# TRN_Open_Servo.net
KiCad netlist of a schematic drawn in EAGLE
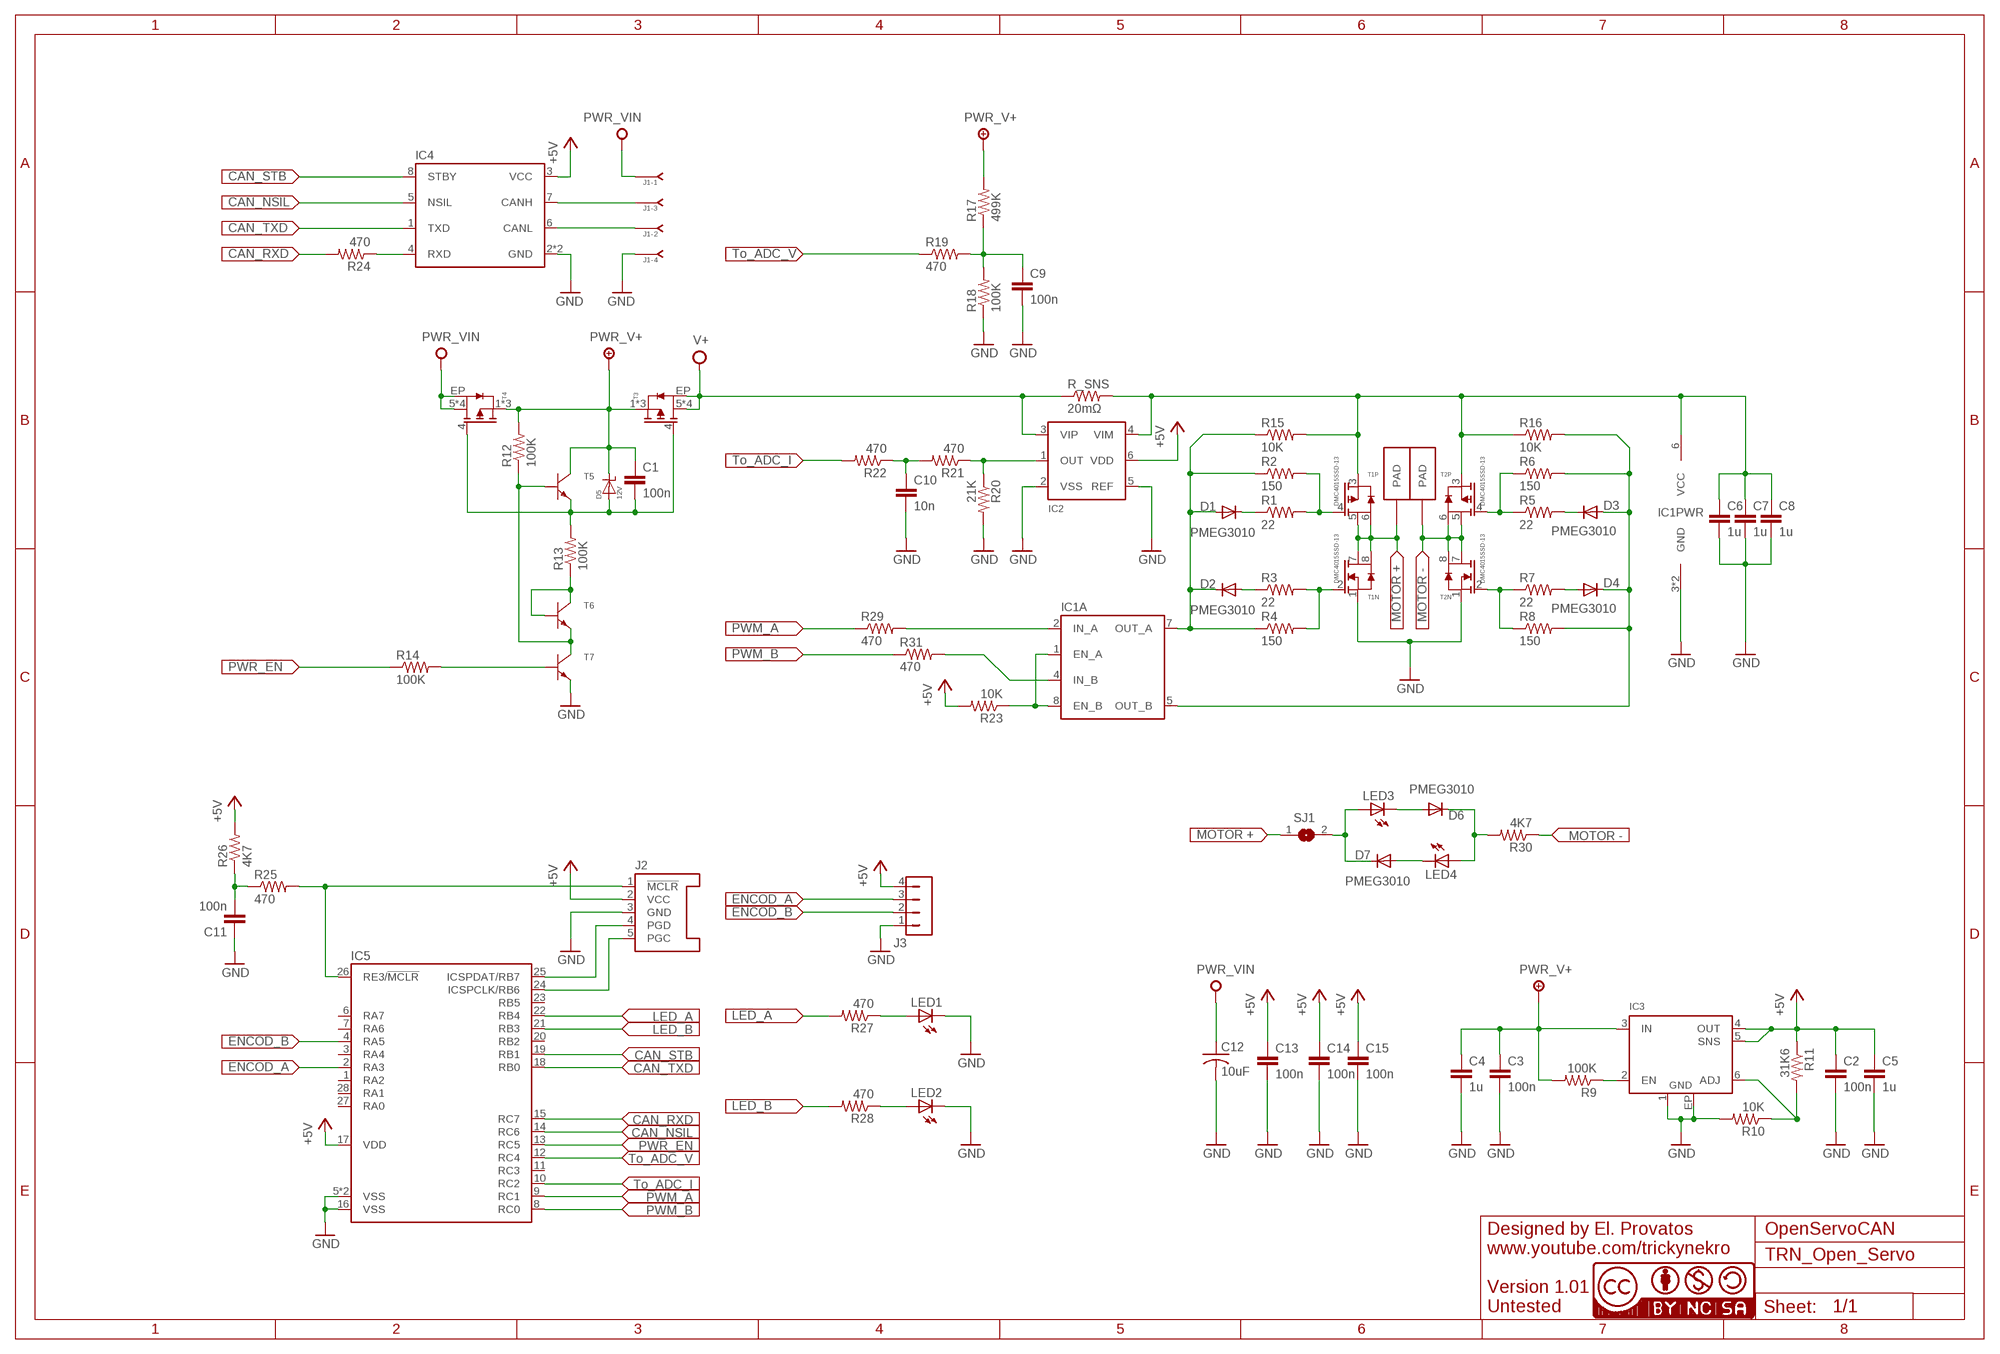
[diagram p0: schematic, sheet 1]

(export (version "E")
  (design (tool "Eeschema 10.0.6"))
  (components
    (comp (ref "C1")
      (value "100n")
      (footprint "eagle-import:C0402")
      (libsource (lib "eagle-import") (part "C-EUC0402"))
    )
    (comp (ref "C2")
      (value "100n")
      (footprint "eagle-import:C0402")
      (libsource (lib "eagle-import") (part "C-EUC0402"))
    )
    (comp (ref "C3")
      (value "100n")
      (footprint "eagle-import:C0402")
      (libsource (lib "eagle-import") (part "C-EUC0402"))
    )
    (comp (ref "C4")
      (value "1u")
      (footprint "eagle-import:C0603K")
      (libsource (lib "eagle-import") (part "C-EUC0603K"))
    )
    (comp (ref "C5")
      (value "1u")
      (footprint "eagle-import:C0603K")
      (libsource (lib "eagle-import") (part "C-EUC0603K"))
    )
    (comp (ref "C6")
      (value "1u")
      (footprint "eagle-import:C0603K")
      (libsource (lib "eagle-import") (part "C-EUC0603K"))
    )
    (comp (ref "C7")
      (value "1u")
      (footprint "eagle-import:C0603K")
      (libsource (lib "eagle-import") (part "C-EUC0603K"))
    )
    (comp (ref "C8")
      (value "1u")
      (footprint "eagle-import:C0603K")
      (libsource (lib "eagle-import") (part "C-EUC0603K"))
    )
    (comp (ref "C9")
      (value "100n")
      (footprint "eagle-import:C0402")
      (libsource (lib "eagle-import") (part "C-EUC0402"))
    )
    (comp (ref "C10")
      (value "10n")
      (footprint "eagle-import:C0402")
      (libsource (lib "eagle-import") (part "C-EUC0402"))
    )
    (comp (ref "C11")
      (value "100n")
      (footprint "eagle-import:C0402")
      (libsource (lib "eagle-import") (part "C-EUC0402"))
    )
    (comp (ref "C12")
      (value "10uF")
      (footprint "eagle-import:C1210")
      (libsource (lib "eagle-import") (part "C-USC1210"))
    )
    (comp (ref "C13")
      (value "100n")
      (footprint "eagle-import:C0402")
      (libsource (lib "eagle-import") (part "C-EUC0402"))
    )
    (comp (ref "C14")
      (value "100n")
      (footprint "eagle-import:C0402")
      (libsource (lib "eagle-import") (part "C-EUC0402"))
    )
    (comp (ref "C15")
      (value "100n")
      (footprint "eagle-import:C0402")
      (libsource (lib "eagle-import") (part "C-EUC0402"))
    )
    (comp (ref "D1")
      (value "PMEG3010")
      (footprint "eagle-import:SOD523")
      (libsource (lib "eagle-import") (part "DIODE-SOD523"))
    )
    (comp (ref "D2")
      (value "PMEG3010")
      (footprint "eagle-import:SOD523")
      (libsource (lib "eagle-import") (part "DIODE-SOD523"))
    )
    (comp (ref "D3")
      (value "PMEG3010")
      (footprint "eagle-import:SOD523")
      (libsource (lib "eagle-import") (part "DIODE-SOD523"))
    )
    (comp (ref "D4")
      (value "PMEG3010")
      (footprint "eagle-import:SOD523")
      (libsource (lib "eagle-import") (part "DIODE-SOD523"))
    )
    (comp (ref "D5")
      (value "12V")
      (footprint "eagle-import:SOD-323")
      (libsource (lib "eagle-import") (part "DDZ12CSF"))
    )
    (comp (ref "D6")
      (value "PMEG3010")
      (footprint "eagle-import:SOD523")
      (libsource (lib "eagle-import") (part "DIODE-SOD523"))
    )
    (comp (ref "D7")
      (value "PMEG3010")
      (footprint "eagle-import:SOD523")
      (libsource (lib "eagle-import") (part "DIODE-SOD523"))
    )
    (comp (ref "IC1")
      (value "MCP14A0454MNY")
      (footprint "eagle-import:TDFN-8-EP")
      (libsource (lib "eagle-import") (part "MCP14A0454MNY"))
    )
    (comp (ref "IC2")
      (value "MCP6C02SMD")
      (footprint "eagle-import:SOT-23-6")
      (libsource (lib "eagle-import") (part "MCP6C02SMD"))
    )
    (comp (ref "IC3")
      (value "LDO40L-ADJ")
      (footprint "eagle-import:DFN6-3X3")
      (libsource (lib "eagle-import") (part "LDO40L-ADJ"))
    )
    (comp (ref "IC4")
      (value "ATA6560GB")
      (footprint "eagle-import:VDFN-8-EP")
      (libsource (lib "eagle-import") (part "ATA6560GB"))
    )
    (comp (ref "IC5")
      (value "PIC18F26K83ML")
      (footprint "eagle-import:QFN-28")
      (libsource (lib "eagle-import") (part "PIC18F26K83ML"))
    )
    (comp (ref "J1")
      (value "J-04-SIP-100")
      (footprint "eagle-import:SIP-100-04")
      (libsource (lib "eagle-import") (part "J-04-SIP-100"))
    )
    (comp (ref "J2")
      (value "PIC-ICSP-MICRO")
      (footprint "eagle-import:PICOBLADE-5")
      (libsource (lib "eagle-import") (part "PIC-ICSP-MICRO"))
    )
    (comp (ref "J3")
      (value "1X4_PICOBLADE_CONNECTOR")
      (footprint "eagle-import:PICOBLADE-4")
      (libsource (lib "eagle-import") (part "1X4_PICOBLADE_CONNECTOR"))
    )
    (comp (ref "LED1")
      (value "LEDCHIP-LED0603")
      (footprint "eagle-import:CHIP-LED0603")
      (libsource (lib "eagle-import") (part "LEDCHIP-LED0603"))
    )
    (comp (ref "LED2")
      (value "LEDCHIP-LED0603")
      (footprint "eagle-import:CHIP-LED0603")
      (libsource (lib "eagle-import") (part "LEDCHIP-LED0603"))
    )
    (comp (ref "LED3")
      (value "LEDCHIP-LED0603")
      (footprint "eagle-import:CHIP-LED0603")
      (libsource (lib "eagle-import") (part "LEDCHIP-LED0603"))
    )
    (comp (ref "LED4")
      (value "LEDCHIP-LED0603")
      (footprint "eagle-import:CHIP-LED0603")
      (libsource (lib "eagle-import") (part "LEDCHIP-LED0603"))
    )
    (comp (ref "PAD1")
      (value "PLATED_SLOT")
      (footprint "eagle-import:PLATED_SLOT")
      (libsource (lib "eagle-import") (part "PLATED_SLOT"))
    )
    (comp (ref "PAD2")
      (value "PLATED_SLOT")
      (footprint "eagle-import:PLATED_SLOT")
      (libsource (lib "eagle-import") (part "PLATED_SLOT"))
    )
    (comp (ref "R1")
      (value "22")
      (footprint "eagle-import:R0402")
      (libsource (lib "eagle-import") (part "R-US_R0402"))
    )
    (comp (ref "R2")
      (value "150")
      (footprint "eagle-import:R0402")
      (libsource (lib "eagle-import") (part "R-US_R0402"))
    )
    (comp (ref "R3")
      (value "22")
      (footprint "eagle-import:R0402")
      (libsource (lib "eagle-import") (part "R-US_R0402"))
    )
    (comp (ref "R4")
      (value "150")
      (footprint "eagle-import:R0402")
      (libsource (lib "eagle-import") (part "R-US_R0402"))
    )
    (comp (ref "R5")
      (value "22")
      (footprint "eagle-import:R0402")
      (libsource (lib "eagle-import") (part "R-US_R0402"))
    )
    (comp (ref "R6")
      (value "150")
      (footprint "eagle-import:R0402")
      (libsource (lib "eagle-import") (part "R-US_R0402"))
    )
    (comp (ref "R7")
      (value "22")
      (footprint "eagle-import:R0402")
      (libsource (lib "eagle-import") (part "R-US_R0402"))
    )
    (comp (ref "R8")
      (value "150")
      (footprint "eagle-import:R0402")
      (libsource (lib "eagle-import") (part "R-US_R0402"))
    )
    (comp (ref "R9")
      (value "100K")
      (footprint "eagle-import:R0402")
      (libsource (lib "eagle-import") (part "R-US_R0402"))
    )
    (comp (ref "R10")
      (value "10K")
      (footprint "eagle-import:R0402")
      (libsource (lib "eagle-import") (part "R-US_R0402"))
    )
    (comp (ref "R11")
      (value "31K6")
      (footprint "eagle-import:R0402")
      (libsource (lib "eagle-import") (part "R-US_R0402"))
    )
    (comp (ref "R12")
      (value "100K")
      (footprint "eagle-import:R0402")
      (libsource (lib "eagle-import") (part "R-US_R0402"))
    )
    (comp (ref "R13")
      (value "100K")
      (footprint "eagle-import:R0402")
      (libsource (lib "eagle-import") (part "R-US_R0402"))
    )
    (comp (ref "R14")
      (value "100K")
      (footprint "eagle-import:R0402")
      (libsource (lib "eagle-import") (part "R-US_R0402"))
    )
    (comp (ref "R15")
      (value "10K")
      (footprint "eagle-import:R0402")
      (libsource (lib "eagle-import") (part "R-US_R0402"))
    )
    (comp (ref "R16")
      (value "10K")
      (footprint "eagle-import:R0402")
      (libsource (lib "eagle-import") (part "R-US_R0402"))
    )
    (comp (ref "R17")
      (value "499K")
      (footprint "eagle-import:R0402")
      (libsource (lib "eagle-import") (part "R-US_R0402"))
    )
    (comp (ref "R18")
      (value "100K")
      (footprint "eagle-import:R0402")
      (libsource (lib "eagle-import") (part "R-US_R0402"))
    )
    (comp (ref "R19")
      (value "470")
      (footprint "eagle-import:R0402")
      (libsource (lib "eagle-import") (part "R-US_R0402"))
    )
    (comp (ref "R20")
      (value "21K")
      (footprint "eagle-import:R0402")
      (libsource (lib "eagle-import") (part "R-US_R0402"))
    )
    (comp (ref "R21")
      (value "470")
      (footprint "eagle-import:R0402")
      (libsource (lib "eagle-import") (part "R-US_R0402"))
    )
    (comp (ref "R22")
      (value "470")
      (footprint "eagle-import:R0402")
      (libsource (lib "eagle-import") (part "R-US_R0402"))
    )
    (comp (ref "R23")
      (value "10K")
      (footprint "eagle-import:R0402")
      (libsource (lib "eagle-import") (part "R-US_R0402"))
    )
    (comp (ref "R24")
      (value "470")
      (footprint "eagle-import:R0402")
      (libsource (lib "eagle-import") (part "R-US_R0402"))
    )
    (comp (ref "R25")
      (value "470")
      (footprint "eagle-import:R0402")
      (libsource (lib "eagle-import") (part "R-US_R0402"))
    )
    (comp (ref "R26")
      (value "4K7")
      (footprint "eagle-import:R0402")
      (libsource (lib "eagle-import") (part "R-US_R0402"))
    )
    (comp (ref "R27")
      (value "470")
      (footprint "eagle-import:R0402")
      (libsource (lib "eagle-import") (part "R-US_R0402"))
    )
    (comp (ref "R28")
      (value "470")
      (footprint "eagle-import:R0402")
      (libsource (lib "eagle-import") (part "R-US_R0402"))
    )
    (comp (ref "R29")
      (value "470")
      (footprint "eagle-import:R0402")
      (libsource (lib "eagle-import") (part "R-US_R0402"))
    )
    (comp (ref "R30")
      (value "4K7")
      (footprint "eagle-import:R0402")
      (libsource (lib "eagle-import") (part "R-US_R0402"))
    )
    (comp (ref "R31")
      (value "470")
      (footprint "eagle-import:R0402")
      (libsource (lib "eagle-import") (part "R-US_R0402"))
    )
    (comp (ref "R_SNS")
      (value "20mΩ")
      (footprint "eagle-import:R0805")
      (libsource (lib "eagle-import") (part "R-US_R0805"))
    )
    (comp (ref "SJ1") (value "SJ") (footprint "eagle-import:SJ") (libsource (lib "eagle-import") (part "SJ")))
    (comp (ref "T1")
      (value "DMC4015SSD-13")
      (footprint "eagle-import:SO-8")
      (libsource (lib "eagle-import") (part "DMC4015SSD-13"))
    )
    (comp (ref "T2")
      (value "DMC4015SSD-13")
      (footprint "eagle-import:SO-8")
      (libsource (lib "eagle-import") (part "DMC4015SSD-13"))
    )
    (comp (ref "T3")
      (value "SISA01DN")
      (footprint "eagle-import:POWERPAK-1212-8")
      (libsource (lib "eagle-import") (part "SISA01DN"))
    )
    (comp (ref "T4")
      (value "SISA01DN")
      (footprint "eagle-import:POWERPAK-1212-8")
      (libsource (lib "eagle-import") (part "SISA01DN"))
    )
    (comp (ref "T5")
      (value "MMBT2222AM3T5G")
      (footprint "eagle-import:SOT-723-3")
      (libsource (lib "eagle-import") (part "MMBT2222AM3T5G"))
    )
    (comp (ref "T6")
      (value "MMBT2222AM3T5G")
      (footprint "eagle-import:SOT-723-3")
      (libsource (lib "eagle-import") (part "MMBT2222AM3T5G"))
    )
    (comp (ref "T7")
      (value "MMBT2222AM3T5G")
      (footprint "eagle-import:SOT-723-3")
      (libsource (lib "eagle-import") (part "MMBT2222AM3T5G"))
    )
    (comp (ref "U$1")
      (value "CC-NC-BCNIX")
      (footprint "eagle-import:CC-NC-B_NIX")
      (libsource (lib "eagle-import") (part "CC-NC-BCNIX"))
    )
  )
  (nets
    (net (code "1") (name "+5V") (class "Default")
      (node (ref "C13") (pin "1") (pinfunction "1_1") (pintype "passive"))
      (node (ref "C14") (pin "1") (pinfunction "1_1") (pintype "passive"))
      (node (ref "C15") (pin "1") (pinfunction "1_1") (pintype "passive"))
      (node (ref "C2") (pin "1") (pinfunction "1_1") (pintype "passive"))
      (node (ref "C5") (pin "1") (pinfunction "1_1") (pintype "passive"))
      (node (ref "IC2") (pin "6") (pinfunction "VDD_6") (pintype "power_in"))
      (node (ref "IC3") (pin "4") (pinfunction "OUT_4") (pintype "bidirectional"))
      (node (ref "IC3") (pin "5") (pinfunction "SNS_5") (pintype "bidirectional"))
      (node (ref "IC4") (pin "3") (pinfunction "VCC_3") (pintype "power_in"))
      (node (ref "IC5") (pin "17") (pinfunction "VDD_17") (pintype "bidirectional"))
      (node (ref "J2") (pin "2") (pinfunction "VCC_2") (pintype "bidirectional"))
      (node (ref "J3") (pin "4") (pinfunction "P$4_4") (pintype "bidirectional"))
      (node (ref "R11") (pin "1") (pinfunction "1_1") (pintype "passive"))
      (node (ref "R23") (pin "2") (pinfunction "2_2") (pintype "passive"))
      (node (ref "R26") (pin "2") (pinfunction "2_2") (pintype "passive"))
    )
    (net (code "2") (name "/CAN_NSIL") (class "Default")
      (node (ref "IC4") (pin "5") (pinfunction "NSIL_5") (pintype "input"))
      (node (ref "IC5") (pin "14") (pinfunction "RC6_14") (pintype "bidirectional"))
    )
    (net (code "3") (name "/CAN_RXD") (class "Default")
      (node (ref "IC5") (pin "15") (pinfunction "RC7_15") (pintype "bidirectional"))
      (node (ref "R24") (pin "2") (pinfunction "2_2") (pintype "passive"))
    )
    (net (code "4") (name "/CAN_STB") (class "Default")
      (node (ref "IC4") (pin "8") (pinfunction "STBY_8") (pintype "input"))
      (node (ref "IC5") (pin "19") (pinfunction "RB1_19") (pintype "bidirectional"))
    )
    (net (code "5") (name "/CAN_TXD") (class "Default")
      (node (ref "IC4") (pin "1") (pinfunction "TXD_1") (pintype "input"))
      (node (ref "IC5") (pin "18") (pinfunction "RB0_18") (pintype "bidirectional"))
    )
    (net (code "6") (name "/ENCOD_A") (class "Default")
      (node (ref "IC5") (pin "2") (pinfunction "RA3_2") (pintype "bidirectional"))
      (node (ref "J3") (pin "3") (pinfunction "P$3_3") (pintype "bidirectional"))
    )
    (net (code "7") (name "/ENCOD_B") (class "Default")
      (node (ref "IC5") (pin "4") (pinfunction "RA5_4") (pintype "bidirectional"))
      (node (ref "J3") (pin "2") (pinfunction "P$2_2") (pintype "bidirectional"))
    )
    (net (code "8") (name "/LED_A") (class "Default")
      (node (ref "IC5") (pin "22") (pinfunction "RB4_22") (pintype "bidirectional"))
      (node (ref "R27") (pin "2") (pinfunction "2_2") (pintype "passive"))
    )
    (net (code "9") (name "/LED_B") (class "Default")
      (node (ref "IC5") (pin "21") (pinfunction "RB3_21") (pintype "bidirectional"))
      (node (ref "R28") (pin "2") (pinfunction "2_2") (pintype "passive"))
    )
    (net (code "10") (name "/MOTOR+") (class "Default")
      (node (ref "PAD1") (pin "P$1") (pinfunction "PAD_P$1") (pintype "bidirectional"))
      (node (ref "PAD1") (pin "P$2") (pinfunction "PAD_P$2") (pintype "bidirectional"))
      (node (ref "SJ1") (pin "1") (pinfunction "1_1") (pintype "passive"))
      (node (ref "T1") (pin "5") (pinfunction "D_5") (pintype "bidirectional"))
      (node (ref "T1") (pin "6") (pinfunction "D_6") (pintype "bidirectional"))
      (node (ref "T1") (pin "7") (pinfunction "D_7") (pintype "bidirectional"))
      (node (ref "T1") (pin "8") (pinfunction "D_8") (pintype "bidirectional"))
    )
    (net (code "11") (name "/MOTOR-") (class "Default")
      (node (ref "PAD2") (pin "P$1") (pinfunction "PAD_P$1") (pintype "bidirectional"))
      (node (ref "PAD2") (pin "P$2") (pinfunction "PAD_P$2") (pintype "bidirectional"))
      (node (ref "R30") (pin "1") (pinfunction "1_1") (pintype "passive"))
      (node (ref "T2") (pin "5") (pinfunction "D_5") (pintype "bidirectional"))
      (node (ref "T2") (pin "6") (pinfunction "D_6") (pintype "bidirectional"))
      (node (ref "T2") (pin "7") (pinfunction "D_7") (pintype "bidirectional"))
      (node (ref "T2") (pin "8") (pinfunction "D_8") (pintype "bidirectional"))
    )
    (net (code "12") (name "/PWM_A") (class "Default")
      (node (ref "IC5") (pin "9") (pinfunction "RC1_9") (pintype "bidirectional"))
      (node (ref "R29") (pin "1") (pinfunction "1_1") (pintype "passive"))
    )
    (net (code "13") (name "/PWM_B") (class "Default")
      (node (ref "IC5") (pin "8") (pinfunction "RC0_8") (pintype "bidirectional"))
      (node (ref "R31") (pin "1") (pinfunction "1_1") (pintype "passive"))
    )
    (net (code "14") (name "/PWR_EN") (class "Default")
      (node (ref "IC5") (pin "13") (pinfunction "RC5_13") (pintype "bidirectional"))
      (node (ref "R14") (pin "1") (pinfunction "1_1") (pintype "passive"))
    )
    (net (code "15") (name "/TO_ADC_I") (class "Default")
      (node (ref "IC5") (pin "10") (pinfunction "RC2_10") (pintype "bidirectional"))
      (node (ref "R22") (pin "2") (pinfunction "2_2") (pintype "passive"))
    )
    (net (code "16") (name "/TO_ADC_V") (class "Default")
      (node (ref "IC5") (pin "12") (pinfunction "RC4_12") (pintype "bidirectional"))
      (node (ref "R19") (pin "1") (pinfunction "1_1") (pintype "passive"))
    )
    (net (code "17") (name "GND") (class "Default")
      (node (ref "C10") (pin "2") (pinfunction "2_2") (pintype "passive"))
      (node (ref "C11") (pin "1") (pinfunction "1_1") (pintype "passive"))
      (node (ref "C12") (pin "2") (pinfunction "2_2") (pintype "passive"))
      (node (ref "C13") (pin "2") (pinfunction "2_2") (pintype "passive"))
      (node (ref "C14") (pin "2") (pinfunction "2_2") (pintype "passive"))
      (node (ref "C15") (pin "2") (pinfunction "2_2") (pintype "passive"))
      (node (ref "C2") (pin "2") (pinfunction "2_2") (pintype "passive"))
      (node (ref "C3") (pin "2") (pinfunction "2_2") (pintype "passive"))
      (node (ref "C4") (pin "2") (pinfunction "2_2") (pintype "passive"))
      (node (ref "C5") (pin "2") (pinfunction "2_2") (pintype "passive"))
      (node (ref "C6") (pin "2") (pinfunction "2_2") (pintype "passive"))
      (node (ref "C7") (pin "2") (pinfunction "2_2") (pintype "passive"))
      (node (ref "C8") (pin "2") (pinfunction "2_2") (pintype "passive"))
      (node (ref "C9") (pin "2") (pinfunction "2_2") (pintype "passive"))
      (node (ref "IC1") (pin "3") (pinfunction "GND_3") (pintype "power_in"))
      (node (ref "IC1") (pin "EP") (pinfunction "GND_EP") (pintype "power_in"))
      (node (ref "IC2") (pin "2") (pinfunction "VSS_2") (pintype "power_in"))
      (node (ref "IC2") (pin "5") (pinfunction "REF_5") (pintype "input"))
      (node (ref "IC3") (pin "1") (pinfunction "GND_1") (pintype "bidirectional"))
      (node (ref "IC3") (pin "EP") (pinfunction "GND_EP") (pintype "bidirectional"))
      (node (ref "IC4") (pin "2") (pinfunction "GND_2") (pintype "power_in"))
      (node (ref "IC4") (pin "EP") (pinfunction "GND_EP") (pintype "power_in"))
      (node (ref "IC5") (pin "16") (pinfunction "VSS_16") (pintype "bidirectional"))
      (node (ref "IC5") (pin "5") (pinfunction "VSS_5") (pintype "bidirectional"))
      (node (ref "IC5") (pin "EP") (pinfunction "VSS_EP") (pintype "bidirectional"))
      (node (ref "J1") (pin "4") (pinfunction "J_4") (pintype "passive"))
      (node (ref "J2") (pin "3") (pinfunction "GND_3") (pintype "bidirectional"))
      (node (ref "J3") (pin "1") (pinfunction "P$1_1") (pintype "bidirectional"))
      (node (ref "LED1") (pin "C") (pinfunction "C_C") (pintype "passive"))
      (node (ref "LED2") (pin "C") (pinfunction "C_C") (pintype "passive"))
      (node (ref "R10") (pin "2") (pinfunction "2_2") (pintype "passive"))
      (node (ref "R18") (pin "1") (pinfunction "1_1") (pintype "passive"))
      (node (ref "R20") (pin "2") (pinfunction "2_2") (pintype "passive"))
      (node (ref "T1") (pin "1") (pinfunction "S_1") (pintype "bidirectional"))
      (node (ref "T2") (pin "1") (pinfunction "S_1") (pintype "bidirectional"))
      (node (ref "T7") (pin "2") (pinfunction "E_2") (pintype "bidirectional"))
    )
    (net (code "18") (name "Net-(C9-Pad1)") (class "Default")
      (node (ref "C9") (pin "1") (pinfunction "1_1") (pintype "passive"))
      (node (ref "R17") (pin "1") (pinfunction "1_1") (pintype "passive"))
      (node (ref "R18") (pin "2") (pinfunction "2_2") (pintype "passive"))
      (node (ref "R19") (pin "2") (pinfunction "2_2") (pintype "passive"))
    )
    (net (code "19") (name "Net-(C10-Pad1)") (class "Default")
      (node (ref "C10") (pin "1") (pinfunction "1_1") (pintype "passive"))
      (node (ref "R21") (pin "2") (pinfunction "2_2") (pintype "passive"))
      (node (ref "R22") (pin "1") (pinfunction "1_1") (pintype "passive"))
    )
    (net (code "20") (name "Net-(C11-Pad2)") (class "Default")
      (node (ref "C11") (pin "2") (pinfunction "2_2") (pintype "passive"))
      (node (ref "R25") (pin "1") (pinfunction "1_1") (pintype "passive"))
      (node (ref "R26") (pin "1") (pinfunction "1_1") (pintype "passive"))
    )
    (net (code "21") (name "Net-(D1-PadC)") (class "Default")
      (node (ref "D1") (pin "C") (pinfunction "C_C") (pintype "passive"))
      (node (ref "R1") (pin "1") (pinfunction "1_1") (pintype "passive"))
    )
    (net (code "22") (name "Net-(D2-PadA)") (class "Default")
      (node (ref "D2") (pin "A") (pinfunction "A_A") (pintype "passive"))
      (node (ref "R3") (pin "1") (pinfunction "1_1") (pintype "passive"))
    )
    (net (code "23") (name "Net-(D3-PadC)") (class "Default")
      (node (ref "D3") (pin "C") (pinfunction "C_C") (pintype "passive"))
      (node (ref "R5") (pin "2") (pinfunction "2_2") (pintype "passive"))
    )
    (net (code "24") (name "Net-(D4-PadA)") (class "Default")
      (node (ref "D4") (pin "A") (pinfunction "A_A") (pintype "passive"))
      (node (ref "R7") (pin "2") (pinfunction "2_2") (pintype "passive"))
    )
    (net (code "25") (name "Net-(D6-PadA)") (class "Default")
      (node (ref "D6") (pin "A") (pinfunction "A_A") (pintype "passive"))
      (node (ref "LED3") (pin "C") (pinfunction "C_C") (pintype "passive"))
    )
    (net (code "26") (name "Net-(D6-PadC)") (class "Default")
      (node (ref "D6") (pin "C") (pinfunction "C_C") (pintype "passive"))
      (node (ref "LED4") (pin "A") (pinfunction "A_A") (pintype "passive"))
      (node (ref "R30") (pin "2") (pinfunction "2_2") (pintype "passive"))
    )
    (net (code "27") (name "Net-(D7-PadA)") (class "Default")
      (node (ref "D7") (pin "A") (pinfunction "A_A") (pintype "passive"))
      (node (ref "LED4") (pin "C") (pinfunction "C_C") (pintype "passive"))
    )
    (net (code "28") (name "Net-(D7-PadC)") (class "Default")
      (node (ref "D7") (pin "C") (pinfunction "C_C") (pintype "passive"))
      (node (ref "LED3") (pin "A") (pinfunction "A_A") (pintype "passive"))
      (node (ref "SJ1") (pin "2") (pinfunction "2_2") (pintype "passive"))
    )
    (net (code "29") (name "Net-(IC1A-EN_A)") (class "Default")
      (node (ref "IC1") (pin "1") (pinfunction "EN_A_1") (pintype "input"))
      (node (ref "IC1") (pin "8") (pinfunction "EN_B_8") (pintype "input"))
      (node (ref "R23") (pin "1") (pinfunction "1_1") (pintype "passive"))
    )
    (net (code "30") (name "Net-(IC1A-IN_A)") (class "Default")
      (node (ref "IC1") (pin "2") (pinfunction "IN_A_2") (pintype "input"))
      (node (ref "R29") (pin "2") (pinfunction "2_2") (pintype "passive"))
    )
    (net (code "31") (name "Net-(IC1A-IN_B)") (class "Default")
      (node (ref "IC1") (pin "4") (pinfunction "IN_B_4") (pintype "input"))
      (node (ref "R31") (pin "2") (pinfunction "2_2") (pintype "passive"))
    )
    (net (code "32") (name "Net-(IC1A-OUT_A)") (class "Default")
      (node (ref "D1") (pin "A") (pinfunction "A_A") (pintype "passive"))
      (node (ref "D2") (pin "C") (pinfunction "C_C") (pintype "passive"))
      (node (ref "IC1") (pin "7") (pinfunction "OUT_A_7") (pintype "output"))
      (node (ref "R15") (pin "1") (pinfunction "1_1") (pintype "passive"))
      (node (ref "R2") (pin "1") (pinfunction "1_1") (pintype "passive"))
      (node (ref "R4") (pin "1") (pinfunction "1_1") (pintype "passive"))
    )
    (net (code "33") (name "Net-(IC1A-OUT_B)") (class "Default")
      (node (ref "D3") (pin "A") (pinfunction "A_A") (pintype "passive"))
      (node (ref "D4") (pin "C") (pinfunction "C_C") (pintype "passive"))
      (node (ref "IC1") (pin "5") (pinfunction "OUT_B_5") (pintype "output"))
      (node (ref "R16") (pin "2") (pinfunction "2_2") (pintype "passive"))
      (node (ref "R6") (pin "2") (pinfunction "2_2") (pintype "passive"))
      (node (ref "R8") (pin "2") (pinfunction "2_2") (pintype "passive"))
    )
    (net (code "34") (name "Net-(IC1B-VCC)") (class "Default")
      (node (ref "C6") (pin "1") (pinfunction "1_1") (pintype "passive"))
      (node (ref "C7") (pin "1") (pinfunction "1_1") (pintype "passive"))
      (node (ref "C8") (pin "1") (pinfunction "1_1") (pintype "passive"))
      (node (ref "IC1") (pin "6") (pinfunction "VCC_6") (pintype "power_in"))
      (node (ref "IC2") (pin "4") (pinfunction "VIM_4") (pintype "input"))
      (node (ref "R15") (pin "2") (pinfunction "2_2") (pintype "passive"))
      (node (ref "R16") (pin "1") (pinfunction "1_1") (pintype "passive"))
      (node (ref "R_SNS") (pin "2") (pinfunction "2_2") (pintype "passive"))
      (node (ref "T1") (pin "3") (pinfunction "S_3") (pintype "bidirectional"))
      (node (ref "T2") (pin "3") (pinfunction "S_3") (pintype "bidirectional"))
    )
    (net (code "35") (name "Net-(IC2-OUT)") (class "Default")
      (node (ref "IC2") (pin "1") (pinfunction "OUT_1") (pintype "output"))
      (node (ref "R20") (pin "1") (pinfunction "1_1") (pintype "passive"))
      (node (ref "R21") (pin "1") (pinfunction "1_1") (pintype "passive"))
    )
    (net (code "36") (name "Net-(IC3-ADJ)") (class "Default")
      (node (ref "IC3") (pin "6") (pinfunction "ADJ_6") (pintype "bidirectional"))
      (node (ref "R10") (pin "1") (pinfunction "1_1") (pintype "passive"))
      (node (ref "R11") (pin "2") (pinfunction "2_2") (pintype "passive"))
    )
    (net (code "37") (name "Net-(IC3-EN)") (class "Default")
      (node (ref "IC3") (pin "2") (pinfunction "EN_2") (pintype "bidirectional"))
      (node (ref "R9") (pin "1") (pinfunction "1_1") (pintype "passive"))
    )
    (net (code "38") (name "Net-(IC4-CANH)") (class "Default")
      (node (ref "IC4") (pin "7") (pinfunction "CANH_7") (pintype "bidirectional"))
      (node (ref "J1") (pin "3") (pinfunction "J_3") (pintype "passive"))
    )
    (net (code "39") (name "Net-(IC4-CANL)") (class "Default")
      (node (ref "IC4") (pin "6") (pinfunction "CANL_6") (pintype "bidirectional"))
      (node (ref "J1") (pin "2") (pinfunction "J_2") (pintype "passive"))
    )
    (net (code "40") (name "Net-(IC4-RXD)") (class "Default")
      (node (ref "IC4") (pin "4") (pinfunction "RXD_4") (pintype "output"))
      (node (ref "R24") (pin "1") (pinfunction "1_1") (pintype "passive"))
    )
    (net (code "41") (name "Net-(IC5-ICSPCLK{slash}RB6)") (class "Default")
      (node (ref "IC5") (pin "24") (pinfunction "ICSPCLK/RB6_24") (pintype "bidirectional"))
      (node (ref "J2") (pin "5") (pinfunction "PGC_5") (pintype "bidirectional"))
    )
    (net (code "42") (name "Net-(IC5-ICSPDAT{slash}RB7)") (class "Default")
      (node (ref "IC5") (pin "25") (pinfunction "ICSPDAT/RB7_25") (pintype "bidirectional"))
      (node (ref "J2") (pin "4") (pinfunction "PGD_4") (pintype "bidirectional"))
    )
    (net (code "43") (name "Net-(IC5-RE3{slash}~{MCLR})") (class "Default")
      (node (ref "IC5") (pin "26") (pinfunction "RE3/~{MCLR}_26") (pintype "bidirectional"))
      (node (ref "J2") (pin "1") (pinfunction "~{MCLR}_1") (pintype "bidirectional"))
      (node (ref "R25") (pin "2") (pinfunction "2_2") (pintype "passive"))
    )
    (net (code "44") (name "Net-(LED1-PadA)") (class "Default")
      (node (ref "LED1") (pin "A") (pinfunction "A_A") (pintype "passive"))
      (node (ref "R27") (pin "1") (pinfunction "1_1") (pintype "passive"))
    )
    (net (code "45") (name "Net-(LED2-PadA)") (class "Default")
      (node (ref "LED2") (pin "A") (pinfunction "A_A") (pintype "passive"))
      (node (ref "R28") (pin "1") (pinfunction "1_1") (pintype "passive"))
    )
    (net (code "46") (name "Net-(T1A-G)") (class "Default")
      (node (ref "R3") (pin "2") (pinfunction "2_2") (pintype "passive"))
      (node (ref "R4") (pin "2") (pinfunction "2_2") (pintype "passive"))
      (node (ref "T1") (pin "2") (pinfunction "G_2") (pintype "bidirectional"))
    )
    (net (code "47") (name "Net-(T1B-G)") (class "Default")
      (node (ref "R1") (pin "2") (pinfunction "2_2") (pintype "passive"))
      (node (ref "R2") (pin "2") (pinfunction "2_2") (pintype "passive"))
      (node (ref "T1") (pin "4") (pinfunction "G_4") (pintype "bidirectional"))
    )
    (net (code "48") (name "Net-(T2A-G)") (class "Default")
      (node (ref "R7") (pin "1") (pinfunction "1_1") (pintype "passive"))
      (node (ref "R8") (pin "1") (pinfunction "1_1") (pintype "passive"))
      (node (ref "T2") (pin "2") (pinfunction "G_2") (pintype "bidirectional"))
    )
    (net (code "49") (name "Net-(T2B-G)") (class "Default")
      (node (ref "R5") (pin "1") (pinfunction "1_1") (pintype "passive"))
      (node (ref "R6") (pin "1") (pinfunction "1_1") (pintype "passive"))
      (node (ref "T2") (pin "4") (pinfunction "G_4") (pintype "bidirectional"))
    )
    (net (code "50") (name "Net-(T3-G)") (class "Default")
      (node (ref "C1") (pin "2") (pinfunction "2_2") (pintype "passive"))
      (node (ref "D5") (pin "A") (pinfunction "A_A") (pintype "bidirectional"))
      (node (ref "R13") (pin "2") (pinfunction "2_2") (pintype "passive"))
      (node (ref "T3") (pin "4") (pinfunction "G_4") (pintype "bidirectional"))
      (node (ref "T4") (pin "4") (pinfunction "G_4") (pintype "bidirectional"))
      (node (ref "T5") (pin "2") (pinfunction "E_2") (pintype "bidirectional"))
    )
    (net (code "51") (name "Net-(T5-B)") (class "Default")
      (node (ref "R12") (pin "1") (pinfunction "1_1") (pintype "passive"))
      (node (ref "T5") (pin "1") (pinfunction "B_1") (pintype "bidirectional"))
      (node (ref "T6") (pin "2") (pinfunction "E_2") (pintype "bidirectional"))
      (node (ref "T7") (pin "3") (pinfunction "C_3") (pintype "bidirectional"))
    )
    (net (code "52") (name "Net-(T6-B)") (class "Default")
      (node (ref "R13") (pin "1") (pinfunction "1_1") (pintype "passive"))
      (node (ref "T6") (pin "1") (pinfunction "B_1") (pintype "bidirectional"))
      (node (ref "T6") (pin "3") (pinfunction "C_3") (pintype "bidirectional"))
    )
    (net (code "53") (name "Net-(T7-B)") (class "Default")
      (node (ref "R14") (pin "2") (pinfunction "2_2") (pintype "passive"))
      (node (ref "T7") (pin "1") (pinfunction "B_1") (pintype "bidirectional"))
    )
    (net (code "54") (name "PWR_V+") (class "Default")
      (node (ref "C1") (pin "1") (pinfunction "1_1") (pintype "passive"))
      (node (ref "C3") (pin "1") (pinfunction "1_1") (pintype "passive"))
      (node (ref "C4") (pin "1") (pinfunction "1_1") (pintype "passive"))
      (node (ref "D5") (pin "K") (pinfunction "K_K") (pintype "bidirectional"))
      (node (ref "IC3") (pin "3") (pinfunction "IN_3") (pintype "bidirectional"))
      (node (ref "R12") (pin "2") (pinfunction "2_2") (pintype "passive"))
      (node (ref "R17") (pin "2") (pinfunction "2_2") (pintype "passive"))
      (node (ref "R9") (pin "2") (pinfunction "2_2") (pintype "passive"))
      (node (ref "T3") (pin "1") (pinfunction "S_1") (pintype "bidirectional"))
      (node (ref "T3") (pin "2") (pinfunction "S_2") (pintype "bidirectional"))
      (node (ref "T3") (pin "3") (pinfunction "S_3") (pintype "bidirectional"))
      (node (ref "T4") (pin "1") (pinfunction "S_1") (pintype "bidirectional"))
      (node (ref "T4") (pin "2") (pinfunction "S_2") (pintype "bidirectional"))
      (node (ref "T4") (pin "3") (pinfunction "S_3") (pintype "bidirectional"))
      (node (ref "T5") (pin "3") (pinfunction "C_3") (pintype "bidirectional"))
    )
    (net (code "55") (name "PWR_VIN") (class "Default")
      (node (ref "C12") (pin "1") (pinfunction "1_1") (pintype "passive"))
      (node (ref "J1") (pin "1") (pinfunction "J_1") (pintype "passive"))
      (node (ref "T4") (pin "5") (pinfunction "D_5") (pintype "bidirectional"))
      (node (ref "T4") (pin "6") (pinfunction "D_6") (pintype "bidirectional"))
      (node (ref "T4") (pin "7") (pinfunction "D_7") (pintype "bidirectional"))
      (node (ref "T4") (pin "8") (pinfunction "D_8") (pintype "bidirectional"))
      (node (ref "T4") (pin "EP") (pinfunction "D_EP") (pintype "bidirectional"))
    )
    (net (code "56") (name "V+") (class "Default")
      (node (ref "IC2") (pin "3") (pinfunction "VIP_3") (pintype "input"))
      (node (ref "R_SNS") (pin "1") (pinfunction "1_1") (pintype "passive"))
      (node (ref "T3") (pin "5") (pinfunction "D_5") (pintype "bidirectional"))
      (node (ref "T3") (pin "6") (pinfunction "D_6") (pintype "bidirectional"))
      (node (ref "T3") (pin "7") (pinfunction "D_7") (pintype "bidirectional"))
      (node (ref "T3") (pin "8") (pinfunction "D_8") (pintype "bidirectional"))
      (node (ref "T3") (pin "EP") (pinfunction "D_EP") (pintype "bidirectional"))
    )
    (net (code "57") (name "unconnected-(IC5-RA0-Pad27)") (class "Default")
      (node (ref "IC5") (pin "27") (pinfunction "RA0_27") (pintype "bidirectional"))
    )
    (net (code "58") (name "unconnected-(IC5-RA1-Pad28)") (class "Default")
      (node (ref "IC5") (pin "28") (pinfunction "RA1_28") (pintype "bidirectional"))
    )
    (net (code "59") (name "unconnected-(IC5-RA2-Pad1)") (class "Default")
      (node (ref "IC5") (pin "1") (pinfunction "RA2_1") (pintype "bidirectional"))
    )
    (net (code "60") (name "unconnected-(IC5-RA4-Pad3)") (class "Default")
      (node (ref "IC5") (pin "3") (pinfunction "RA4_3") (pintype "bidirectional"))
    )
    (net (code "61") (name "unconnected-(IC5-RA6-Pad7)") (class "Default")
      (node (ref "IC5") (pin "7") (pinfunction "RA6_7") (pintype "bidirectional"))
    )
    (net (code "62") (name "unconnected-(IC5-RA7-Pad6)") (class "Default")
      (node (ref "IC5") (pin "6") (pinfunction "RA7_6") (pintype "bidirectional"))
    )
    (net (code "63") (name "unconnected-(IC5-RB2-Pad20)") (class "Default")
      (node (ref "IC5") (pin "20") (pinfunction "RB2_20") (pintype "bidirectional"))
    )
    (net (code "64") (name "unconnected-(IC5-RB5-Pad23)") (class "Default")
      (node (ref "IC5") (pin "23") (pinfunction "RB5_23") (pintype "bidirectional"))
    )
    (net (code "65") (name "unconnected-(IC5-RC3-Pad11)") (class "Default")
      (node (ref "IC5") (pin "11") (pinfunction "RC3_11") (pintype "bidirectional"))
    )
  )
)
